# easyeda.net
KiCad netlist of a schematic drawn in EasyEDA
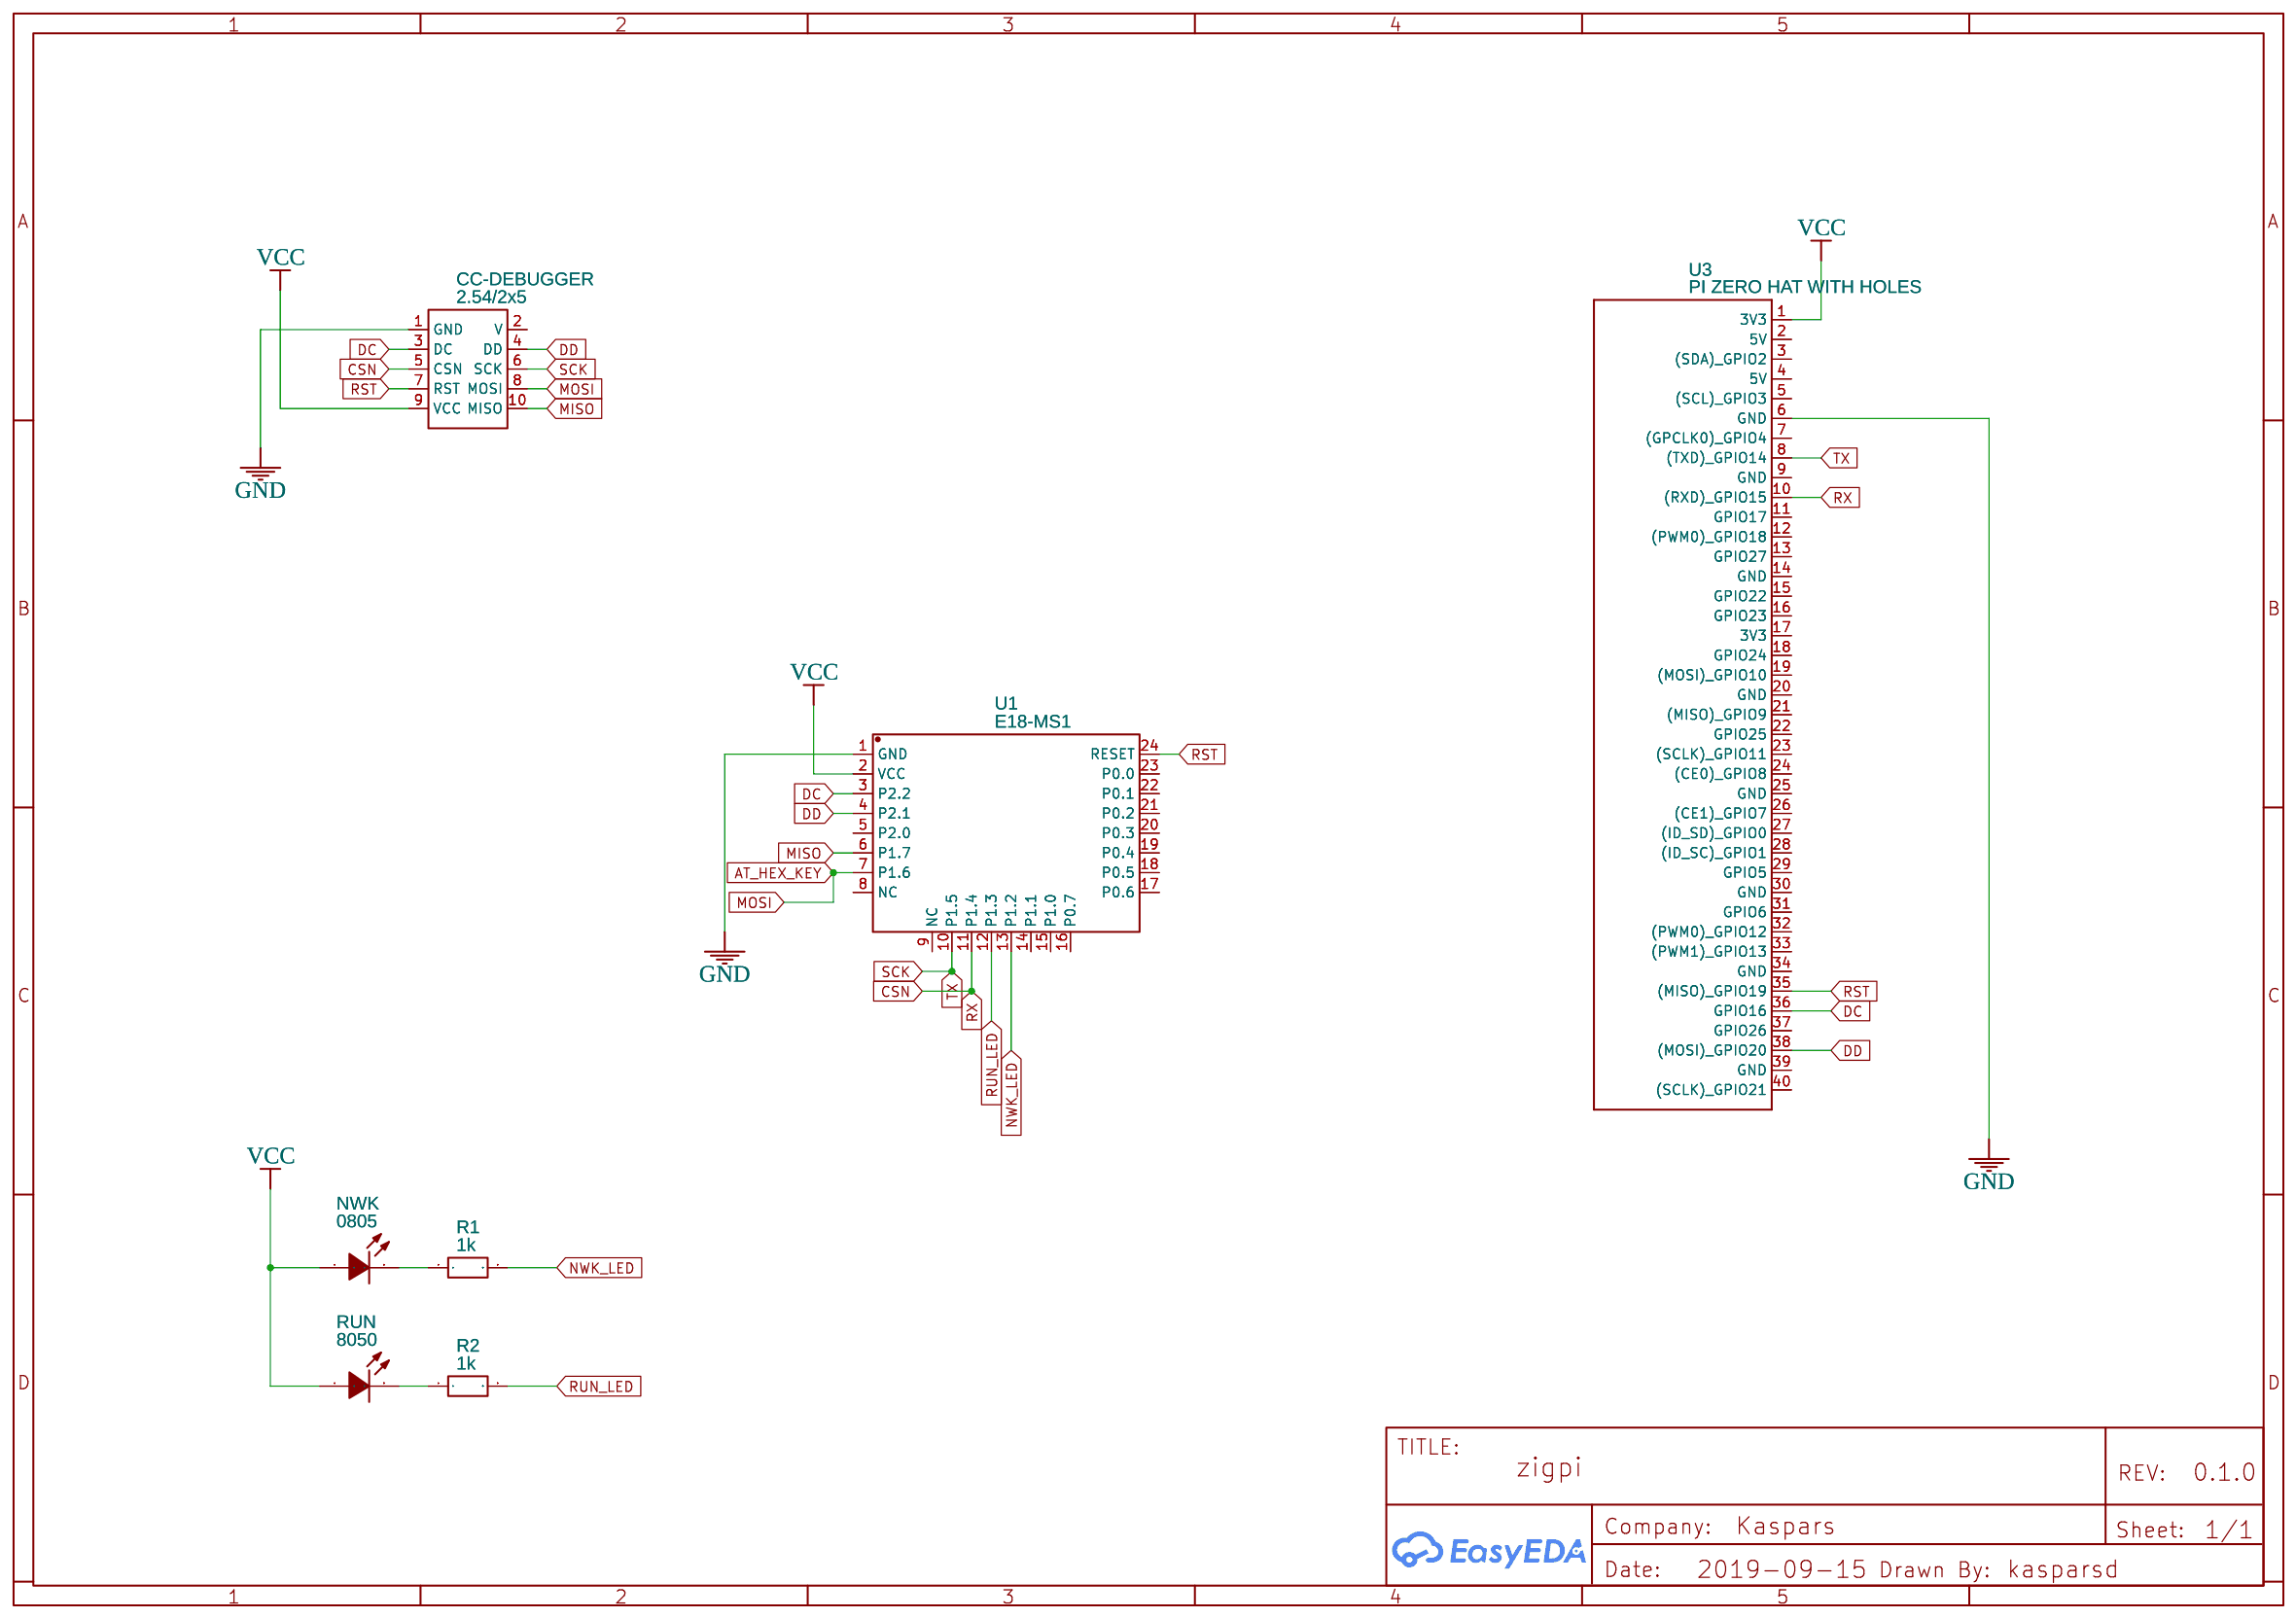
[diagram p0: schematic sheet]

(export (version "E")
  (design (tool "Eeschema 10.0.6"))
  (components
    (comp (ref "CC-DEBUGGER")
      (value "2.54/2x5")
      (fields
        (field (name "BOM_Manufacturer Part") "220S-2*5P H=8.5MM Ytype Gold-plated")
        (field (name "BOM_Supplier Part") "C124423")
      )
      (libsource (lib "") (part "Header-Female-2.54_2x5"))
    )
    (comp (ref "NWK")
      (value "0805")
      (fields
        (field (name "BOM_Manufacturer Part") "D-W080508W1-KS2")
        (field (name "BOM_Supplier Part") "C130115")
      )
      (libsource (lib "") (part "D-W080508W1-KS2"))
    )
    (comp (ref "R1") (value "1k") (libsource (lib "") (part "Res_0805(1/8W)_EU")))
    (comp (ref "R2") (value "1k") (libsource (lib "") (part "Res_0805(1/8W)_EU")))
    (comp (ref "RUN")
      (value "8050")
      (fields
        (field (name "BOM_Manufacturer Part") "D-W080508W1-KS2")
        (field (name "BOM_Supplier Part") "C130115")
      )
      (libsource (lib "") (part "D-W080508W1-KS2_1"))
    )
    (comp (ref "U1")
      (value "E18-MS1")
      (fields
        (field (name "BOM_Manufacturer Part") "E18-MS1-PCB")
        (field (name "BOM_Supplier Part") "C97344")
      )
      (libsource (lib "") (part "Unknown_505_420"))
    )
    (comp (ref "U3")
      (value "PI ZERO HAT WITH HOLES")
      (fields (field (name "BOM_Manufacturer Part") "RaspberryPi 3"))
      (libsource (lib "") (part "PI ZERO HAT WITH HOLES"))
    )
  )
  (nets
    (net (code "1") (name "AT_HEX_KEY") (class "Default")
      (node (ref "CC-DEBUGGER") (pin "8") (pinfunction "MOSI_8") (pintype "unspecified"))
      (node (ref "U1") (pin "7") (pinfunction "P1.6_7") (pintype "unspecified"))
    )
    (net (code "2") (name "CSN") (class "Default")
      (node (ref "CC-DEBUGGER") (pin "5") (pinfunction "CSN_5") (pintype "unspecified"))
      (node (ref "U1") (pin "11") (pinfunction "P1.4_11") (pintype "unspecified"))
      (node (ref "U3") (pin "10") (pinfunction "(RXD)_GPIO15_10") (pintype "unspecified"))
    )
    (net (code "3") (name "DC") (class "Default")
      (node (ref "CC-DEBUGGER") (pin "3") (pinfunction "DC_3") (pintype "unspecified"))
      (node (ref "U1") (pin "3") (pinfunction "P2.2_3") (pintype "unspecified"))
      (node (ref "U3") (pin "36") (pinfunction "GPIO16_36") (pintype "unspecified"))
    )
    (net (code "4") (name "DD") (class "Default")
      (node (ref "CC-DEBUGGER") (pin "4") (pinfunction "DD_4") (pintype "unspecified"))
      (node (ref "U1") (pin "4") (pinfunction "P2.1_4") (pintype "unspecified"))
      (node (ref "U3") (pin "38") (pinfunction "(MOSI)_GPIO20_38") (pintype "unspecified"))
    )
    (net (code "5") (name "GND") (class "Default")
      (node (ref "CC-DEBUGGER") (pin "1") (pinfunction "GND_1") (pintype "unspecified"))
      (node (ref "U1") (pin "1") (pinfunction "GND_1") (pintype "unspecified"))
      (node (ref "U3") (pin "6") (pinfunction "GND_6") (pintype "unspecified"))
    )
    (net (code "6") (name "MISO") (class "Default")
      (node (ref "CC-DEBUGGER") (pin "10") (pinfunction "MISO_10") (pintype "unspecified"))
      (node (ref "U1") (pin "6") (pinfunction "P1.7_6") (pintype "unspecified"))
    )
    (net (code "7") (name "NWK_LED") (class "Default")
      (node (ref "R1") (pin "2") (pinfunction "2_2") (pintype "unspecified"))
      (node (ref "U1") (pin "13") (pinfunction "P1.2_13") (pintype "unspecified"))
    )
    (net (code "8") (name "Net-(NWK-K)") (class "Default")
      (node (ref "NWK") (pin "2") (pinfunction "K_2") (pintype "unspecified"))
      (node (ref "R1") (pin "1") (pinfunction "1_1") (pintype "unspecified"))
    )
    (net (code "9") (name "Net-(RUN-K)") (class "Default")
      (node (ref "R2") (pin "1") (pinfunction "1_1") (pintype "unspecified"))
      (node (ref "RUN") (pin "2") (pinfunction "K_2") (pintype "unspecified"))
    )
    (net (code "10") (name "RST") (class "Default")
      (node (ref "CC-DEBUGGER") (pin "7") (pinfunction "RST_7") (pintype "unspecified"))
      (node (ref "U1") (pin "24") (pinfunction "RESET_24") (pintype "unspecified"))
      (node (ref "U3") (pin "35") (pinfunction "(MISO)_GPIO19_35") (pintype "unspecified"))
    )
    (net (code "11") (name "RUN_LED") (class "Default")
      (node (ref "R2") (pin "2") (pinfunction "2_2") (pintype "unspecified"))
      (node (ref "U1") (pin "12") (pinfunction "P1.3_12") (pintype "unspecified"))
    )
    (net (code "12") (name "SCK") (class "Default")
      (node (ref "CC-DEBUGGER") (pin "6") (pinfunction "SCK_6") (pintype "unspecified"))
      (node (ref "U1") (pin "10") (pinfunction "P1.5_10") (pintype "unspecified"))
      (node (ref "U3") (pin "8") (pinfunction "(TXD)_GPIO14_8") (pintype "unspecified"))
    )
    (net (code "13") (name "VCC") (class "Default")
      (node (ref "CC-DEBUGGER") (pin "9") (pinfunction "VCC_9") (pintype "unspecified"))
      (node (ref "NWK") (pin "1") (pinfunction "A_1") (pintype "unspecified"))
      (node (ref "RUN") (pin "1") (pinfunction "A_1") (pintype "unspecified"))
      (node (ref "U1") (pin "2") (pinfunction "VCC_2") (pintype "unspecified"))
      (node (ref "U3") (pin "1") (pinfunction "3V3_1") (pintype "unspecified"))
    )
    (net (code "14") (name "unconnected-(CC-DEBUGGER-V-Pad2)") (class "Default")
      (node (ref "CC-DEBUGGER") (pin "2") (pinfunction "V_2") (pintype "unspecified"))
    )
    (net (code "15") (name "unconnected-(U1-NC-Pad8)") (class "Default")
      (node (ref "U1") (pin "8") (pinfunction "NC_8") (pintype "unspecified"))
    )
    (net (code "16") (name "unconnected-(U1-NC-Pad9)") (class "Default")
      (node (ref "U1") (pin "9") (pinfunction "NC_9") (pintype "unspecified"))
    )
    (net (code "17") (name "unconnected-(U1-P0.0-Pad23)") (class "Default")
      (node (ref "U1") (pin "23") (pinfunction "P0.0_23") (pintype "unspecified"))
    )
    (net (code "18") (name "unconnected-(U1-P0.1-Pad22)") (class "Default")
      (node (ref "U1") (pin "22") (pinfunction "P0.1_22") (pintype "unspecified"))
    )
    (net (code "19") (name "unconnected-(U1-P0.2-Pad21)") (class "Default")
      (node (ref "U1") (pin "21") (pinfunction "P0.2_21") (pintype "unspecified"))
    )
    (net (code "20") (name "unconnected-(U1-P0.3-Pad20)") (class "Default")
      (node (ref "U1") (pin "20") (pinfunction "P0.3_20") (pintype "unspecified"))
    )
    (net (code "21") (name "unconnected-(U1-P0.4-Pad19)") (class "Default")
      (node (ref "U1") (pin "19") (pinfunction "P0.4_19") (pintype "unspecified"))
    )
    (net (code "22") (name "unconnected-(U1-P0.5-Pad18)") (class "Default")
      (node (ref "U1") (pin "18") (pinfunction "P0.5_18") (pintype "unspecified"))
    )
    (net (code "23") (name "unconnected-(U1-P0.6-Pad17)") (class "Default")
      (node (ref "U1") (pin "17") (pinfunction "P0.6_17") (pintype "unspecified"))
    )
    (net (code "24") (name "unconnected-(U1-P0.7-Pad16)") (class "Default")
      (node (ref "U1") (pin "16") (pinfunction "P0.7_16") (pintype "unspecified"))
    )
    (net (code "25") (name "unconnected-(U1-P1.0-Pad15)") (class "Default")
      (node (ref "U1") (pin "15") (pinfunction "P1.0_15") (pintype "unspecified"))
    )
    (net (code "26") (name "unconnected-(U1-P1.1-Pad14)") (class "Default")
      (node (ref "U1") (pin "14") (pinfunction "P1.1_14") (pintype "unspecified"))
    )
    (net (code "27") (name "unconnected-(U1-P2.0-Pad5)") (class "Default")
      (node (ref "U1") (pin "5") (pinfunction "P2.0_5") (pintype "unspecified"))
    )
    (net (code "28") (name "unconnected-(U3-(CE0)_GPIO8-Pad24)") (class "Default")
      (node (ref "U3") (pin "24") (pinfunction "(CE0)_GPIO8_24") (pintype "unspecified"))
    )
    (net (code "29") (name "unconnected-(U3-(CE1)_GPIO7-Pad26)") (class "Default")
      (node (ref "U3") (pin "26") (pinfunction "(CE1)_GPIO7_26") (pintype "unspecified"))
    )
    (net (code "30") (name "unconnected-(U3-(GPCLK0)_GPIO4-Pad7)") (class "Default")
      (node (ref "U3") (pin "7") (pinfunction "(GPCLK0)_GPIO4_7") (pintype "unspecified"))
    )
    (net (code "31") (name "unconnected-(U3-(ID_SC)_GPIO1-Pad28)") (class "Default")
      (node (ref "U3") (pin "28") (pinfunction "(ID_SC)_GPIO1_28") (pintype "unspecified"))
    )
    (net (code "32") (name "unconnected-(U3-(ID_SD)_GPIO0-Pad27)") (class "Default")
      (node (ref "U3") (pin "27") (pinfunction "(ID_SD)_GPIO0_27") (pintype "unspecified"))
    )
    (net (code "33") (name "unconnected-(U3-(MISO)_GPIO9-Pad21)") (class "Default")
      (node (ref "U3") (pin "21") (pinfunction "(MISO)_GPIO9_21") (pintype "unspecified"))
    )
    (net (code "34") (name "unconnected-(U3-(MOSI)_GPIO10-Pad19)") (class "Default")
      (node (ref "U3") (pin "19") (pinfunction "(MOSI)_GPIO10_19") (pintype "unspecified"))
    )
    (net (code "35") (name "unconnected-(U3-(PWM0)_GPIO12-Pad32)") (class "Default")
      (node (ref "U3") (pin "32") (pinfunction "(PWM0)_GPIO12_32") (pintype "unspecified"))
    )
    (net (code "36") (name "unconnected-(U3-(PWM0)_GPIO18-Pad12)") (class "Default")
      (node (ref "U3") (pin "12") (pinfunction "(PWM0)_GPIO18_12") (pintype "unspecified"))
    )
    (net (code "37") (name "unconnected-(U3-(PWM1)_GPIO13-Pad33)") (class "Default")
      (node (ref "U3") (pin "33") (pinfunction "(PWM1)_GPIO13_33") (pintype "unspecified"))
    )
    (net (code "38") (name "unconnected-(U3-(SCL)_GPIO3-Pad5)") (class "Default")
      (node (ref "U3") (pin "5") (pinfunction "(SCL)_GPIO3_5") (pintype "unspecified"))
    )
    (net (code "39") (name "unconnected-(U3-(SCLK)_GPIO11-Pad23)") (class "Default")
      (node (ref "U3") (pin "23") (pinfunction "(SCLK)_GPIO11_23") (pintype "unspecified"))
    )
    (net (code "40") (name "unconnected-(U3-(SCLK)_GPIO21-Pad40)") (class "Default")
      (node (ref "U3") (pin "40") (pinfunction "(SCLK)_GPIO21_40") (pintype "unspecified"))
    )
    (net (code "41") (name "unconnected-(U3-(SDA)_GPIO2-Pad3)") (class "Default")
      (node (ref "U3") (pin "3") (pinfunction "(SDA)_GPIO2_3") (pintype "unspecified"))
    )
    (net (code "42") (name "unconnected-(U3-3V3-Pad17)") (class "Default")
      (node (ref "U3") (pin "17") (pinfunction "3V3_17") (pintype "unspecified"))
    )
    (net (code "43") (name "unconnected-(U3-5V-Pad2)") (class "Default")
      (node (ref "U3") (pin "2") (pinfunction "5V_2") (pintype "unspecified"))
    )
    (net (code "44") (name "unconnected-(U3-5V-Pad4)") (class "Default")
      (node (ref "U3") (pin "4") (pinfunction "5V_4") (pintype "unspecified"))
    )
    (net (code "45") (name "unconnected-(U3-GND-Pad9)") (class "Default")
      (node (ref "U3") (pin "9") (pinfunction "GND_9") (pintype "unspecified"))
    )
    (net (code "46") (name "unconnected-(U3-GND-Pad14)") (class "Default")
      (node (ref "U3") (pin "14") (pinfunction "GND_14") (pintype "unspecified"))
    )
    (net (code "47") (name "unconnected-(U3-GND-Pad20)") (class "Default")
      (node (ref "U3") (pin "20") (pinfunction "GND_20") (pintype "unspecified"))
    )
    (net (code "48") (name "unconnected-(U3-GND-Pad25)") (class "Default")
      (node (ref "U3") (pin "25") (pinfunction "GND_25") (pintype "unspecified"))
    )
    (net (code "49") (name "unconnected-(U3-GND-Pad30)") (class "Default")
      (node (ref "U3") (pin "30") (pinfunction "GND_30") (pintype "unspecified"))
    )
    (net (code "50") (name "unconnected-(U3-GND-Pad34)") (class "Default")
      (node (ref "U3") (pin "34") (pinfunction "GND_34") (pintype "unspecified"))
    )
    (net (code "51") (name "unconnected-(U3-GND-Pad39)") (class "Default")
      (node (ref "U3") (pin "39") (pinfunction "GND_39") (pintype "unspecified"))
    )
    (net (code "52") (name "unconnected-(U3-GPIO5-Pad29)") (class "Default")
      (node (ref "U3") (pin "29") (pinfunction "GPIO5_29") (pintype "unspecified"))
    )
    (net (code "53") (name "unconnected-(U3-GPIO6-Pad31)") (class "Default")
      (node (ref "U3") (pin "31") (pinfunction "GPIO6_31") (pintype "unspecified"))
    )
    (net (code "54") (name "unconnected-(U3-GPIO17-Pad11)") (class "Default")
      (node (ref "U3") (pin "11") (pinfunction "GPIO17_11") (pintype "unspecified"))
    )
    (net (code "55") (name "unconnected-(U3-GPIO22-Pad15)") (class "Default")
      (node (ref "U3") (pin "15") (pinfunction "GPIO22_15") (pintype "unspecified"))
    )
    (net (code "56") (name "unconnected-(U3-GPIO23-Pad16)") (class "Default")
      (node (ref "U3") (pin "16") (pinfunction "GPIO23_16") (pintype "unspecified"))
    )
    (net (code "57") (name "unconnected-(U3-GPIO24-Pad18)") (class "Default")
      (node (ref "U3") (pin "18") (pinfunction "GPIO24_18") (pintype "unspecified"))
    )
    (net (code "58") (name "unconnected-(U3-GPIO25-Pad22)") (class "Default")
      (node (ref "U3") (pin "22") (pinfunction "GPIO25_22") (pintype "unspecified"))
    )
    (net (code "59") (name "unconnected-(U3-GPIO26-Pad37)") (class "Default")
      (node (ref "U3") (pin "37") (pinfunction "GPIO26_37") (pintype "unspecified"))
    )
    (net (code "60") (name "unconnected-(U3-GPIO27-Pad13)") (class "Default")
      (node (ref "U3") (pin "13") (pinfunction "GPIO27_13") (pintype "unspecified"))
    )
  )
)
